# DIB_8bit.net
KiCad netlist of a schematic drawn in Altium Designer
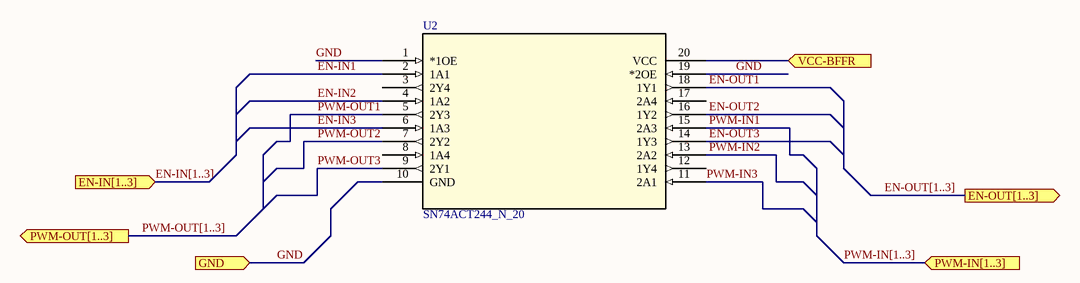
[diagram p0: DIB_8bit.SchDoc]

(export (version "E")
  (design (tool "Eeschema 10.0.6"))
  (components
    (comp (ref "U2")
      (value "SN74ACT244_N_20")
      (footprint "DW20-M")
      (description "Imported")
      (fields
        (field (name "MANUFACTURER") "Texas Instruments")
        (field (name "GENERIC_PART_NUMBER") "SN74ACT244")
      )
      (libsource (lib "2016-10-29_23-20-10") (part "SN74ACT244_N_20"))
    )
  )
  (nets
    (net (code "1") (name "/EN-IN1") (class "Default")
      (node (ref "U2") (pin "2") (pinfunction "1A1_2") (pintype "input"))
    )
    (net (code "2") (name "/EN-IN2") (class "Default")
      (node (ref "U2") (pin "4") (pinfunction "1A2_4") (pintype "input"))
    )
    (net (code "3") (name "/EN-IN3") (class "Default")
      (node (ref "U2") (pin "6") (pinfunction "1A3_6") (pintype "input"))
    )
    (net (code "5") (name "/EN-OUT1") (class "Default")
      (node (ref "U2") (pin "18") (pinfunction "1Y1_18") (pintype "output"))
    )
    (net (code "6") (name "/EN-OUT2") (class "Default")
      (node (ref "U2") (pin "16") (pinfunction "1Y2_16") (pintype "output"))
    )
    (net (code "7") (name "/EN-OUT3") (class "Default")
      (node (ref "U2") (pin "14") (pinfunction "1Y3_14") (pintype "output"))
    )
    (net (code "9") (name "/GND") (class "Default")
      (node (ref "U2") (pin "1") (pinfunction "*1OE_1") (pintype "input"))
      (node (ref "U2") (pin "10") (pinfunction "GND_10") (pintype "power_in"))
      (node (ref "U2") (pin "19") (pinfunction "*2OE_19") (pintype "input"))
    )
    (net (code "10") (name "/PWM-IN1") (class "Default")
      (node (ref "U2") (pin "15") (pinfunction "2A3_15") (pintype "input"))
    )
    (net (code "11") (name "/PWM-IN2") (class "Default")
      (node (ref "U2") (pin "13") (pinfunction "2A2_13") (pintype "input"))
    )
    (net (code "12") (name "/PWM-IN3") (class "Default")
      (node (ref "U2") (pin "11") (pinfunction "2A1_11") (pintype "input"))
    )
    (net (code "14") (name "/PWM-OUT1") (class "Default")
      (node (ref "U2") (pin "5") (pinfunction "2Y3_5") (pintype "output"))
    )
    (net (code "15") (name "/PWM-OUT2") (class "Default")
      (node (ref "U2") (pin "7") (pinfunction "2Y2_7") (pintype "output"))
    )
    (net (code "16") (name "/PWM-OUT3") (class "Default")
      (node (ref "U2") (pin "9") (pinfunction "2Y1_9") (pintype "output"))
    )
    (net (code "18") (name "/VCC-BFFR") (class "Default")
      (node (ref "U2") (pin "20") (pinfunction "VCC_20") (pintype "power_in"))
    )
    (net (code "19") (name "unconnected-(U2-1A4-Pad8)") (class "Default")
      (node (ref "U2") (pin "8") (pinfunction "1A4_8") (pintype "input"))
    )
    (net (code "20") (name "unconnected-(U2-1Y4-Pad12)") (class "Default")
      (node (ref "U2") (pin "12") (pinfunction "1Y4_12") (pintype "output"))
    )
    (net (code "21") (name "unconnected-(U2-2A4-Pad17)") (class "Default")
      (node (ref "U2") (pin "17") (pinfunction "2A4_17") (pintype "input"))
    )
    (net (code "22") (name "unconnected-(U2-2Y4-Pad3)") (class "Default")
      (node (ref "U2") (pin "3") (pinfunction "2Y4_3") (pintype "output"))
    )
  )
)
